# 8_BTB.net
KiCad netlist of a schematic drawn in Altium Designer
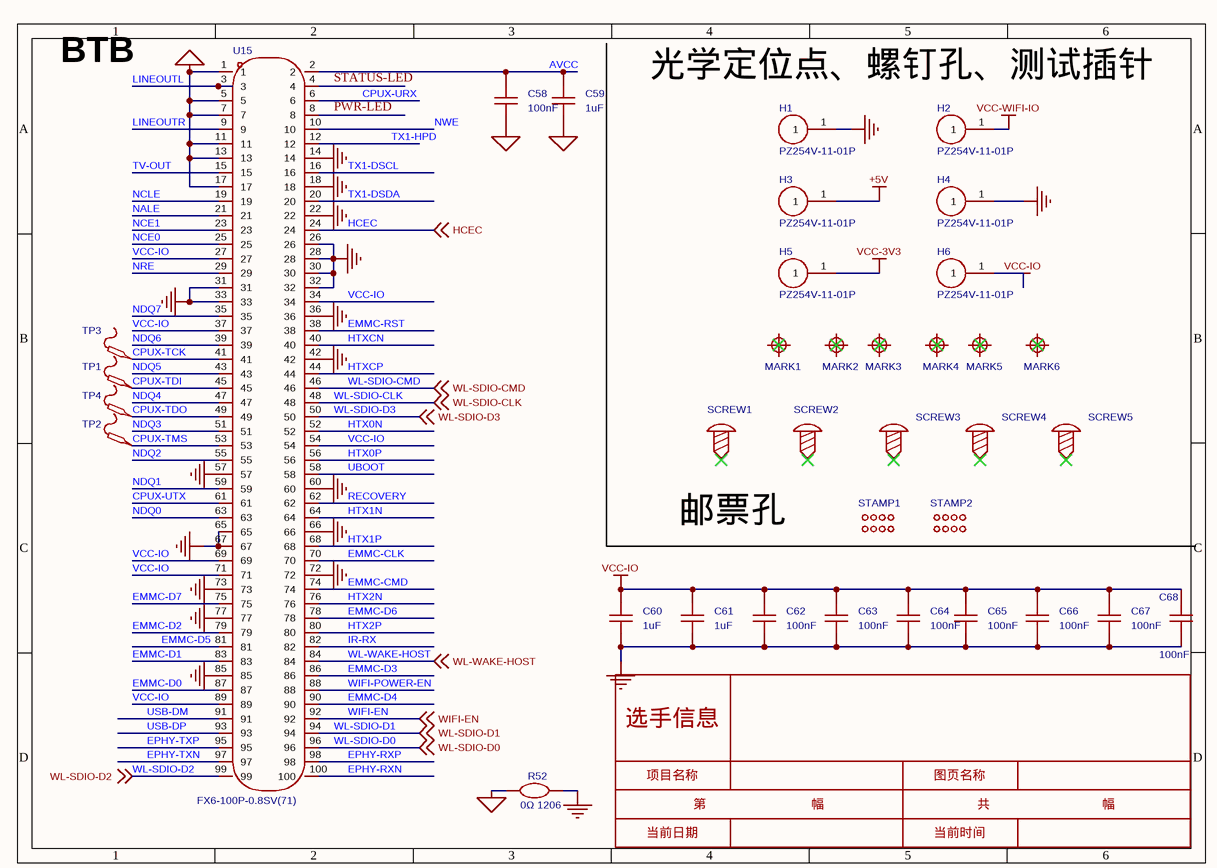
[diagram p0: 8_BTB.schdoc]

(export (version "E")
  (design (tool "Eeschema 10.0.6"))
  (components
    (comp (ref "C58")
      (value "100nF")
      (footprint "C0402")
      (description "容值:100nF;精度:±10%;额定电压:16V;温度系数:X7R;")
      (fields
        (field (name "MANUFACTURER") "SAMSUNG(三星)")
        (field (name "MANUFACTURER PART") "CL05B104KO5NNNC")
      )
      (libsource (lib "altium-import") (part "root_3_CL05B104KO5NNNC_"))
    )
    (comp (ref "C59")
      (value "1uF")
      (footprint "C0402")
      (description "容值:1uF;精度:±10%;额定电压:50V;温度系数:X5R;")
      (fields
        (field (name "MANUFACTURER") "HRE(芯声)")
        (field (name "MANUFACTURER PART") "CGA0402X5R105K500GT")
      )
      (libsource (lib "altium-import") (part "root_3_CGA0402X5R105K500GT_"))
    )
    (comp (ref "C60")
      (value "1uF")
      (footprint "C0402")
      (description "容值:1uF;精度:±10%;额定电压:50V;温度系数:X5R;")
      (fields
        (field (name "MANUFACTURER") "HRE(芯声)")
        (field (name "MANUFACTURER PART") "CGA0402X5R105K500GT")
      )
      (libsource (lib "altium-import") (part "root_3_CGA0402X5R105K500GT_"))
    )
    (comp (ref "C61")
      (value "1uF")
      (footprint "C0402")
      (description "容值:1uF;精度:±10%;额定电压:50V;温度系数:X5R;")
      (fields
        (field (name "MANUFACTURER") "HRE(芯声)")
        (field (name "MANUFACTURER PART") "CGA0402X5R105K500GT")
      )
      (libsource (lib "altium-import") (part "root_3_CGA0402X5R105K500GT_"))
    )
    (comp (ref "C62")
      (value "100nF")
      (footprint "C0402")
      (description "容值:100nF;精度:±10%;额定电压:16V;温度系数:X7R;")
      (fields
        (field (name "MANUFACTURER") "SAMSUNG(三星)")
        (field (name "MANUFACTURER PART") "CL05B104KO5NNNC")
      )
      (libsource (lib "altium-import") (part "root_3_CL05B104KO5NNNC_"))
    )
    (comp (ref "C63")
      (value "100nF")
      (footprint "C0402")
      (description "容值:100nF;精度:±10%;额定电压:16V;温度系数:X7R;")
      (fields
        (field (name "MANUFACTURER") "SAMSUNG(三星)")
        (field (name "MANUFACTURER PART") "CL05B104KO5NNNC")
      )
      (libsource (lib "altium-import") (part "root_3_CL05B104KO5NNNC_"))
    )
    (comp (ref "C64")
      (value "100nF")
      (footprint "C0402")
      (description "容值:100nF;精度:±10%;额定电压:16V;温度系数:X7R;")
      (fields
        (field (name "MANUFACTURER") "SAMSUNG(三星)")
        (field (name "MANUFACTURER PART") "CL05B104KO5NNNC")
      )
      (libsource (lib "altium-import") (part "root_3_CL05B104KO5NNNC_"))
    )
    (comp (ref "C65")
      (value "100nF")
      (footprint "C0402")
      (description "容值:100nF;精度:±10%;额定电压:16V;温度系数:X7R;")
      (fields
        (field (name "MANUFACTURER") "SAMSUNG(三星)")
        (field (name "MANUFACTURER PART") "CL05B104KO5NNNC")
      )
      (libsource (lib "altium-import") (part "root_3_CL05B104KO5NNNC_"))
    )
    (comp (ref "C66")
      (value "100nF")
      (footprint "C0402")
      (description "容值:100nF;精度:±10%;额定电压:16V;温度系数:X7R;")
      (fields
        (field (name "MANUFACTURER") "SAMSUNG(三星)")
        (field (name "MANUFACTURER PART") "CL05B104KO5NNNC")
      )
      (libsource (lib "altium-import") (part "root_3_CL05B104KO5NNNC_"))
    )
    (comp (ref "C67")
      (value "100nF")
      (footprint "C0402")
      (description "容值:100nF;精度:±10%;额定电压:16V;温度系数:X7R;")
      (fields
        (field (name "MANUFACTURER") "SAMSUNG(三星)")
        (field (name "MANUFACTURER PART") "CL05B104KO5NNNC")
      )
      (libsource (lib "altium-import") (part "root_3_CL05B104KO5NNNC_"))
    )
    (comp (ref "C68")
      (value "100nF")
      (footprint "C0402")
      (description "容值:100nF;精度:±10%;额定电压:16V;温度系数:X7R;")
      (fields
        (field (name "MANUFACTURER") "SAMSUNG(三星)")
        (field (name "MANUFACTURER PART") "CL05B104KO5NNNC")
      )
      (libsource (lib "altium-import") (part "root_3_CL05B104KO5NNNC_"))
    )
    (comp (ref "H1")
      (value "PZ254V-11-01P")
      (footprint "HDR-TH_1P-P2.54-V-M")
      (fields (field (name "MANUFACTURER") "XFCN(兴飞)"))
      (libsource (lib "altium-import") (part "root_2_PZ254V-11-01P_"))
    )
    (comp (ref "H2")
      (value "PZ254V-11-01P")
      (footprint "HDR-TH_1P-P2.54-V-M")
      (fields (field (name "MANUFACTURER") "XFCN(兴飞)"))
      (libsource (lib "altium-import") (part "root_2_PZ254V-11-01P_"))
    )
    (comp (ref "H3")
      (value "PZ254V-11-01P")
      (footprint "HDR-TH_1P-P2.54-V-M")
      (fields (field (name "MANUFACTURER") "XFCN(兴飞)"))
      (libsource (lib "altium-import") (part "root_2_PZ254V-11-01P_"))
    )
    (comp (ref "H4")
      (value "PZ254V-11-01P")
      (footprint "HDR-TH_1P-P2.54-V-M")
      (fields (field (name "MANUFACTURER") "XFCN(兴飞)"))
      (libsource (lib "altium-import") (part "root_2_PZ254V-11-01P_"))
    )
    (comp (ref "H5")
      (value "PZ254V-11-01P")
      (footprint "HDR-TH_1P-P2.54-V-M")
      (fields (field (name "MANUFACTURER") "XFCN(兴飞)"))
      (libsource (lib "altium-import") (part "root_2_PZ254V-11-01P_"))
    )
    (comp (ref "H6")
      (value "PZ254V-11-01P")
      (footprint "HDR-TH_1P-P2.54-V-M")
      (fields (field (name "MANUFACTURER") "XFCN(兴飞)"))
      (libsource (lib "altium-import") (part "root_2_PZ254V-11-01P_"))
    )
    (comp (ref "MARK1")
      (value "~")
      (footprint "Mark-Point-1mm")
      (description "Mark点")
      (libsource (lib "altium-import") (part "root_0_Mark-Point_"))
    )
    (comp (ref "MARK2")
      (value "~")
      (footprint "Mark-Point-1mm")
      (description "Mark点")
      (libsource (lib "altium-import") (part "root_0_Mark-Point_"))
    )
    (comp (ref "MARK3")
      (value "~")
      (footprint "Mark-Point-1mm")
      (description "Mark点")
      (libsource (lib "altium-import") (part "root_0_Mark-Point_"))
    )
    (comp (ref "MARK4")
      (value "~")
      (footprint "Mark-Point-1mm")
      (description "Mark点")
      (libsource (lib "altium-import") (part "root_0_Mark-Point_"))
    )
    (comp (ref "MARK5")
      (value "~")
      (footprint "Mark-Point-1mm")
      (description "Mark点")
      (libsource (lib "altium-import") (part "root_0_Mark-Point_"))
    )
    (comp (ref "MARK6")
      (value "~")
      (footprint "Mark-Point-1mm")
      (description "Mark点")
      (libsource (lib "altium-import") (part "root_0_Mark-Point_"))
    )
    (comp (ref "R52")
      (value "0Ω 1206")
      (footprint "R1206")
      (description "电阻类型:厚膜电阻;阻值:0Ω;精度:±5%;功率:250mW;工作电压:200V;")
      (fields (field (name "MANUFACTURER") "FOJAN(富捷)") (field (name "MANUFACTURER PART") "FRC1206P000 TS"))
      (libsource (lib "altium-import") (part "root_0_FRC1206P000 TS_"))
    )
    (comp (ref "SCREW1")
      (value "~")
      (footprint "SIP-1A")
      (libsource (lib "altium-import") (part "root_0_M3螺丝_"))
    )
    (comp (ref "SCREW2")
      (value "~")
      (footprint "SIP-1A")
      (libsource (lib "altium-import") (part "root_0_M3螺丝_"))
    )
    (comp (ref "SCREW3")
      (value "~")
      (footprint "SIP-1A")
      (libsource (lib "altium-import") (part "root_0_M3螺丝_"))
    )
    (comp (ref "SCREW4")
      (value "~")
      (footprint "SIP-1A")
      (libsource (lib "altium-import") (part "root_0_M3螺丝_"))
    )
    (comp (ref "SCREW5")
      (value "~")
      (footprint "SIP-1A")
      (libsource (lib "altium-import") (part "root_0_M3螺丝_"))
    )
    (comp (ref "STAMP1")
      (value "~")
      (footprint "youpiaokong")
      (libsource (lib "altium-import") (part "root_0_youpiaokong_"))
    )
    (comp (ref "STAMP2")
      (value "~")
      (footprint "youpiaokong")
      (libsource (lib "altium-import") (part "root_0_youpiaokong_"))
    )
    (comp (ref "TP1")
      (value "~")
      (footprint "Test-Point-0.5mm")
      (description "Test Point 测试点")
      (libsource (lib "altium-import") (part "root_1_Test-Point_"))
    )
    (comp (ref "TP2")
      (value "~")
      (footprint "Test-Point-0.5mm")
      (description "Test Point 测试点")
      (libsource (lib "altium-import") (part "root_1_Test-Point_"))
    )
    (comp (ref "TP3")
      (value "~")
      (footprint "Test-Point-0.5mm")
      (description "Test Point 测试点")
      (libsource (lib "altium-import") (part "root_1_Test-Point_"))
    )
    (comp (ref "TP4")
      (value "~")
      (footprint "Test-Point-0.5mm")
      (description "Test Point 测试点")
      (libsource (lib "altium-import") (part "root_1_Test-Point_"))
    )
    (comp (ref "U15")
      (value "FX6-100P-0.8SV(71)")
      (footprint "CONN-SMD_100P-P0.80_FX6-100P-0.8SV71")
      (description "额定电流:500mA;工作温度:-55℃~+85℃;")
      (fields (field (name "MANUFACTURER") "HRS(广濑)"))
      (libsource (lib "altium-import") (part "root_0_FX6-100P-0.8SV(71)_"))
    )
  )
  (nets
    (net (code "1") (name "+5V") (class "Default")
      (node (ref "H3") (pin "1") (pinfunction "1_1") (pintype "passive"))
    )
    (net (code "3") (name "/AVCC") (class "Default")
      (node (ref "C58") (pin "1") (pinfunction "1_1") (pintype "passive"))
      (node (ref "C59") (pin "1") (pinfunction "1_1") (pintype "passive"))
      (node (ref "U15") (pin "2") (pinfunction "2_2") (pintype "passive"))
    )
    (net (code "4") (name "/CPUX-TCK") (class "Default")
      (node (ref "TP3") (pin "1") (pinfunction "1_1") (pintype "passive"))
      (node (ref "U15") (pin "41") (pinfunction "41_41") (pintype "passive"))
    )
    (net (code "5") (name "/CPUX-TDI") (class "Default")
      (node (ref "TP1") (pin "1") (pinfunction "1_1") (pintype "passive"))
      (node (ref "U15") (pin "45") (pinfunction "45_45") (pintype "passive"))
    )
    (net (code "6") (name "/CPUX-TDO") (class "Default")
      (node (ref "TP4") (pin "1") (pinfunction "1_1") (pintype "passive"))
      (node (ref "U15") (pin "49") (pinfunction "49_49") (pintype "passive"))
    )
    (net (code "7") (name "/CPUX-TMS") (class "Default")
      (node (ref "TP2") (pin "1") (pinfunction "1_1") (pintype "passive"))
      (node (ref "U15") (pin "53") (pinfunction "53_53") (pintype "passive"))
    )
    (net (code "8") (name "/CPUX-URX") (class "Default")
      (node (ref "U15") (pin "6") (pinfunction "6_6") (pintype "passive"))
    )
    (net (code "9") (name "/CPUX-UTX") (class "Default")
      (node (ref "U15") (pin "61") (pinfunction "61_61") (pintype "passive"))
    )
    (net (code "10") (name "/EMMC-CLK") (class "Default")
      (node (ref "U15") (pin "70") (pinfunction "70_70") (pintype "passive"))
    )
    (net (code "11") (name "/EMMC-CMD") (class "Default")
      (node (ref "U15") (pin "74") (pinfunction "74_74") (pintype "passive"))
    )
    (net (code "12") (name "/EMMC-D0") (class "Default")
      (node (ref "U15") (pin "87") (pinfunction "87_87") (pintype "passive"))
    )
    (net (code "13") (name "/EMMC-D1") (class "Default")
      (node (ref "U15") (pin "83") (pinfunction "83_83") (pintype "passive"))
    )
    (net (code "14") (name "/EMMC-D2") (class "Default")
      (node (ref "U15") (pin "79") (pinfunction "79_79") (pintype "passive"))
    )
    (net (code "15") (name "/EMMC-D3") (class "Default")
      (node (ref "U15") (pin "86") (pinfunction "86_86") (pintype "passive"))
    )
    (net (code "16") (name "/EMMC-D4") (class "Default")
      (node (ref "U15") (pin "90") (pinfunction "90_90") (pintype "passive"))
    )
    (net (code "17") (name "/EMMC-D5") (class "Default")
      (node (ref "U15") (pin "81") (pinfunction "81_81") (pintype "passive"))
    )
    (net (code "18") (name "/EMMC-D6") (class "Default")
      (node (ref "U15") (pin "78") (pinfunction "78_78") (pintype "passive"))
    )
    (net (code "19") (name "/EMMC-D7") (class "Default")
      (node (ref "U15") (pin "75") (pinfunction "75_75") (pintype "passive"))
    )
    (net (code "20") (name "/EMMC-RST") (class "Default")
      (node (ref "U15") (pin "38") (pinfunction "38_38") (pintype "passive"))
    )
    (net (code "21") (name "/EPHY-RXN") (class "Default")
      (node (ref "U15") (pin "100") (pinfunction "100_100") (pintype "passive"))
    )
    (net (code "22") (name "/EPHY-RXP") (class "Default")
      (node (ref "U15") (pin "98") (pinfunction "98_98") (pintype "passive"))
    )
    (net (code "23") (name "/EPHY-TXN") (class "Default")
      (node (ref "U15") (pin "97") (pinfunction "97_97") (pintype "passive"))
    )
    (net (code "24") (name "/EPHY-TXP") (class "Default")
      (node (ref "U15") (pin "95") (pinfunction "95_95") (pintype "passive"))
    )
    (net (code "25") (name "/HTX0N") (class "Default")
      (node (ref "U15") (pin "52") (pinfunction "52_52") (pintype "passive"))
    )
    (net (code "26") (name "/HTX0P") (class "Default")
      (node (ref "U15") (pin "56") (pinfunction "56_56") (pintype "passive"))
    )
    (net (code "27") (name "/HTX1N") (class "Default")
      (node (ref "U15") (pin "64") (pinfunction "64_64") (pintype "passive"))
    )
    (net (code "28") (name "/HTX1P") (class "Default")
      (node (ref "U15") (pin "68") (pinfunction "68_68") (pintype "passive"))
    )
    (net (code "29") (name "/HTX2N") (class "Default")
      (node (ref "U15") (pin "76") (pinfunction "76_76") (pintype "passive"))
    )
    (net (code "30") (name "/HTX2P") (class "Default")
      (node (ref "U15") (pin "80") (pinfunction "80_80") (pintype "passive"))
    )
    (net (code "31") (name "/HTXCN") (class "Default")
      (node (ref "U15") (pin "40") (pinfunction "40_40") (pintype "passive"))
    )
    (net (code "32") (name "/HTXCP") (class "Default")
      (node (ref "U15") (pin "44") (pinfunction "44_44") (pintype "passive"))
    )
    (net (code "33") (name "/IR-RX") (class "Default")
      (node (ref "U15") (pin "82") (pinfunction "82_82") (pintype "passive"))
    )
    (net (code "34") (name "/LINEOUTL") (class "Default")
      (node (ref "U15") (pin "3") (pinfunction "3_3") (pintype "passive"))
    )
    (net (code "35") (name "/LINEOUTR") (class "Default")
      (node (ref "U15") (pin "9") (pinfunction "9_9") (pintype "passive"))
    )
    (net (code "36") (name "/NALE") (class "Default")
      (node (ref "U15") (pin "21") (pinfunction "21_21") (pintype "passive"))
    )
    (net (code "37") (name "/NCE0") (class "Default")
      (node (ref "U15") (pin "25") (pinfunction "25_25") (pintype "passive"))
    )
    (net (code "38") (name "/NCE1") (class "Default")
      (node (ref "U15") (pin "23") (pinfunction "23_23") (pintype "passive"))
    )
    (net (code "39") (name "/NCLE") (class "Default")
      (node (ref "U15") (pin "19") (pinfunction "19_19") (pintype "passive"))
    )
    (net (code "40") (name "/NDQ0") (class "Default")
      (node (ref "U15") (pin "63") (pinfunction "63_63") (pintype "passive"))
    )
    (net (code "41") (name "/NDQ1") (class "Default")
      (node (ref "U15") (pin "59") (pinfunction "59_59") (pintype "passive"))
    )
    (net (code "42") (name "/NDQ2") (class "Default")
      (node (ref "U15") (pin "55") (pinfunction "55_55") (pintype "passive"))
    )
    (net (code "43") (name "/NDQ3") (class "Default")
      (node (ref "U15") (pin "51") (pinfunction "51_51") (pintype "passive"))
    )
    (net (code "44") (name "/NDQ4") (class "Default")
      (node (ref "U15") (pin "47") (pinfunction "47_47") (pintype "passive"))
    )
    (net (code "45") (name "/NDQ5") (class "Default")
      (node (ref "U15") (pin "43") (pinfunction "43_43") (pintype "passive"))
    )
    (net (code "46") (name "/NDQ6") (class "Default")
      (node (ref "U15") (pin "39") (pinfunction "39_39") (pintype "passive"))
    )
    (net (code "47") (name "/NDQ7") (class "Default")
      (node (ref "U15") (pin "35") (pinfunction "35_35") (pintype "passive"))
    )
    (net (code "48") (name "/NRE") (class "Default")
      (node (ref "U15") (pin "29") (pinfunction "29_29") (pintype "passive"))
    )
    (net (code "49") (name "/NWE") (class "Default")
      (node (ref "U15") (pin "10") (pinfunction "10_10") (pintype "passive"))
    )
    (net (code "50") (name "/PWR-LED") (class "Default")
      (node (ref "U15") (pin "8") (pinfunction "8_8") (pintype "passive"))
    )
    (net (code "51") (name "/RECOVERY") (class "Default")
      (node (ref "U15") (pin "62") (pinfunction "62_62") (pintype "passive"))
    )
    (net (code "52") (name "/STATUS-LED") (class "Default")
      (node (ref "U15") (pin "4") (pinfunction "4_4") (pintype "passive"))
    )
    (net (code "53") (name "/TV-OUT") (class "Default")
      (node (ref "U15") (pin "15") (pinfunction "15_15") (pintype "passive"))
    )
    (net (code "54") (name "/TX1-DSCL") (class "Default")
      (node (ref "U15") (pin "16") (pinfunction "16_16") (pintype "passive"))
    )
    (net (code "55") (name "/TX1-DSDA") (class "Default")
      (node (ref "U15") (pin "20") (pinfunction "20_20") (pintype "passive"))
    )
    (net (code "56") (name "/TX1-HPD") (class "Default")
      (node (ref "U15") (pin "12") (pinfunction "12_12") (pintype "passive"))
    )
    (net (code "57") (name "/UBOOT") (class "Default")
      (node (ref "U15") (pin "58") (pinfunction "58_58") (pintype "passive"))
    )
    (net (code "58") (name "/USB-DM") (class "Default")
      (node (ref "U15") (pin "91") (pinfunction "91_91") (pintype "passive"))
    )
    (net (code "59") (name "/USB-DP") (class "Default")
      (node (ref "U15") (pin "93") (pinfunction "93_93") (pintype "passive"))
    )
    (net (code "60") (name "/WIFI-POWER-EN") (class "Default")
      (node (ref "U15") (pin "88") (pinfunction "88_88") (pintype "passive"))
    )
    (net (code "61") (name "AGND") (class "Default")
      (node (ref "C58") (pin "2") (pinfunction "2_2") (pintype "passive"))
      (node (ref "C59") (pin "2") (pinfunction "2_2") (pintype "passive"))
      (node (ref "R52") (pin "1") (pinfunction "1_1") (pintype "passive"))
      (node (ref "U15") (pin "1") (pinfunction "1_1") (pintype "passive"))
      (node (ref "U15") (pin "11") (pinfunction "11_11") (pintype "passive"))
      (node (ref "U15") (pin "13") (pinfunction "13_13") (pintype "passive"))
      (node (ref "U15") (pin "17") (pinfunction "17_17") (pintype "passive"))
      (node (ref "U15") (pin "5") (pinfunction "5_5") (pintype "passive"))
      (node (ref "U15") (pin "7") (pinfunction "7_7") (pintype "passive"))
    )
    (net (code "62") (name "GND") (class "Default")
      (node (ref "C60") (pin "2") (pinfunction "2_2") (pintype "passive"))
      (node (ref "C61") (pin "2") (pinfunction "2_2") (pintype "passive"))
      (node (ref "C62") (pin "2") (pinfunction "2_2") (pintype "passive"))
      (node (ref "C63") (pin "2") (pinfunction "2_2") (pintype "passive"))
      (node (ref "C64") (pin "2") (pinfunction "2_2") (pintype "passive"))
      (node (ref "C65") (pin "2") (pinfunction "2_2") (pintype "passive"))
      (node (ref "C66") (pin "2") (pinfunction "2_2") (pintype "passive"))
      (node (ref "C67") (pin "2") (pinfunction "2_2") (pintype "passive"))
      (node (ref "C68") (pin "2") (pinfunction "2_2") (pintype "passive"))
      (node (ref "H1") (pin "1") (pinfunction "1_1") (pintype "passive"))
      (node (ref "H4") (pin "1") (pinfunction "1_1") (pintype "passive"))
      (node (ref "R52") (pin "2") (pinfunction "2_2") (pintype "passive"))
      (node (ref "U15") (pin "14") (pinfunction "14_14") (pintype "passive"))
      (node (ref "U15") (pin "18") (pinfunction "18_18") (pintype "passive"))
      (node (ref "U15") (pin "22") (pinfunction "22_22") (pintype "passive"))
      (node (ref "U15") (pin "26") (pinfunction "26_26") (pintype "passive"))
      (node (ref "U15") (pin "28") (pinfunction "28_28") (pintype "passive"))
      (node (ref "U15") (pin "30") (pinfunction "30_30") (pintype "passive"))
      (node (ref "U15") (pin "31") (pinfunction "31_31") (pintype "passive"))
      (node (ref "U15") (pin "32") (pinfunction "32_32") (pintype "passive"))
      (node (ref "U15") (pin "33") (pinfunction "33_33") (pintype "passive"))
      (node (ref "U15") (pin "36") (pinfunction "36_36") (pintype "passive"))
      (node (ref "U15") (pin "42") (pinfunction "42_42") (pintype "passive"))
      (node (ref "U15") (pin "57") (pinfunction "57_57") (pintype "passive"))
      (node (ref "U15") (pin "60") (pinfunction "60_60") (pintype "passive"))
      (node (ref "U15") (pin "65") (pinfunction "65_65") (pintype "passive"))
      (node (ref "U15") (pin "66") (pinfunction "66_66") (pintype "passive"))
      (node (ref "U15") (pin "67") (pinfunction "67_67") (pintype "passive"))
      (node (ref "U15") (pin "72") (pinfunction "72_72") (pintype "passive"))
      (node (ref "U15") (pin "73") (pinfunction "73_73") (pintype "passive"))
      (node (ref "U15") (pin "77") (pinfunction "77_77") (pintype "passive"))
      (node (ref "U15") (pin "85") (pinfunction "85_85") (pintype "passive"))
    )
    (net (code "63") (name "HCEC") (class "Default")
      (node (ref "U15") (pin "24") (pinfunction "24_24") (pintype "passive"))
    )
    (net (code "64") (name "VCC-3V3") (class "Default")
      (node (ref "H5") (pin "1") (pinfunction "1_1") (pintype "passive"))
    )
    (net (code "65") (name "VCC-IO") (class "Default")
      (node (ref "C60") (pin "1") (pinfunction "1_1") (pintype "passive"))
      (node (ref "C61") (pin "1") (pinfunction "1_1") (pintype "passive"))
      (node (ref "C62") (pin "1") (pinfunction "1_1") (pintype "passive"))
      (node (ref "C63") (pin "1") (pinfunction "1_1") (pintype "passive"))
      (node (ref "C64") (pin "1") (pinfunction "1_1") (pintype "passive"))
      (node (ref "C65") (pin "1") (pinfunction "1_1") (pintype "passive"))
      (node (ref "C66") (pin "1") (pinfunction "1_1") (pintype "passive"))
      (node (ref "C67") (pin "1") (pinfunction "1_1") (pintype "passive"))
      (node (ref "C68") (pin "1") (pinfunction "1_1") (pintype "passive"))
      (node (ref "H6") (pin "1") (pinfunction "1_1") (pintype "passive"))
      (node (ref "U15") (pin "27") (pinfunction "27_27") (pintype "passive"))
      (node (ref "U15") (pin "34") (pinfunction "34_34") (pintype "passive"))
      (node (ref "U15") (pin "37") (pinfunction "37_37") (pintype "passive"))
      (node (ref "U15") (pin "54") (pinfunction "54_54") (pintype "passive"))
      (node (ref "U15") (pin "69") (pinfunction "69_69") (pintype "passive"))
      (node (ref "U15") (pin "71") (pinfunction "71_71") (pintype "passive"))
      (node (ref "U15") (pin "89") (pinfunction "89_89") (pintype "passive"))
    )
    (net (code "66") (name "VCC-WIFI-IO") (class "Default")
      (node (ref "H2") (pin "1") (pinfunction "1_1") (pintype "passive"))
    )
    (net (code "67") (name "WIFI-EN") (class "Default")
      (node (ref "U15") (pin "92") (pinfunction "92_92") (pintype "passive"))
    )
    (net (code "68") (name "WL-SDIO-CLK") (class "Default")
      (node (ref "U15") (pin "48") (pinfunction "48_48") (pintype "passive"))
    )
    (net (code "69") (name "WL-SDIO-CMD") (class "Default")
      (node (ref "U15") (pin "46") (pinfunction "46_46") (pintype "passive"))
    )
    (net (code "70") (name "WL-SDIO-D0") (class "Default")
      (node (ref "U15") (pin "96") (pinfunction "96_96") (pintype "passive"))
    )
    (net (code "71") (name "WL-SDIO-D1") (class "Default")
      (node (ref "U15") (pin "94") (pinfunction "94_94") (pintype "passive"))
    )
    (net (code "72") (name "WL-SDIO-D2") (class "Default")
      (node (ref "U15") (pin "99") (pinfunction "99_99") (pintype "passive"))
    )
    (net (code "73") (name "WL-SDIO-D3") (class "Default")
      (node (ref "U15") (pin "50") (pinfunction "50_50") (pintype "passive"))
    )
    (net (code "74") (name "WL-WAKE-HOST") (class "Default")
      (node (ref "U15") (pin "84") (pinfunction "84_84") (pintype "passive"))
    )
    (net (code "75") (name "unconnected-(MARK1-Pad1)") (class "Default")
      (node (ref "MARK1") (pin "1") (pinfunction "1_1") (pintype "passive+no_connect"))
    )
    (net (code "76") (name "unconnected-(MARK2-Pad1)") (class "Default")
      (node (ref "MARK2") (pin "1") (pinfunction "1_1") (pintype "passive+no_connect"))
    )
    (net (code "77") (name "unconnected-(MARK3-Pad1)") (class "Default")
      (node (ref "MARK3") (pin "1") (pinfunction "1_1") (pintype "passive+no_connect"))
    )
    (net (code "78") (name "unconnected-(MARK4-Pad1)") (class "Default")
      (node (ref "MARK4") (pin "1") (pinfunction "1_1") (pintype "passive+no_connect"))
    )
    (net (code "79") (name "unconnected-(MARK5-Pad1)") (class "Default")
      (node (ref "MARK5") (pin "1") (pinfunction "1_1") (pintype "passive+no_connect"))
    )
    (net (code "80") (name "unconnected-(MARK6-Pad1)") (class "Default")
      (node (ref "MARK6") (pin "1") (pinfunction "1_1") (pintype "passive+no_connect"))
    )
    (net (code "81") (name "unconnected-(SCREW1-Pad1)") (class "Default")
      (node (ref "SCREW1") (pin "1") (pinfunction "1_1") (pintype "passive+no_connect"))
    )
    (net (code "82") (name "unconnected-(SCREW2-Pad1)") (class "Default")
      (node (ref "SCREW2") (pin "1") (pinfunction "1_1") (pintype "passive+no_connect"))
    )
    (net (code "83") (name "unconnected-(SCREW3-Pad1)") (class "Default")
      (node (ref "SCREW3") (pin "1") (pinfunction "1_1") (pintype "passive+no_connect"))
    )
    (net (code "84") (name "unconnected-(SCREW4-Pad1)") (class "Default")
      (node (ref "SCREW4") (pin "1") (pinfunction "1_1") (pintype "passive+no_connect"))
    )
    (net (code "85") (name "unconnected-(SCREW5-Pad1)") (class "Default")
      (node (ref "SCREW5") (pin "1") (pinfunction "1_1") (pintype "passive+no_connect"))
    )
  )
)
